# ADC.net
KiCad netlist of a schematic drawn in Altium Designer
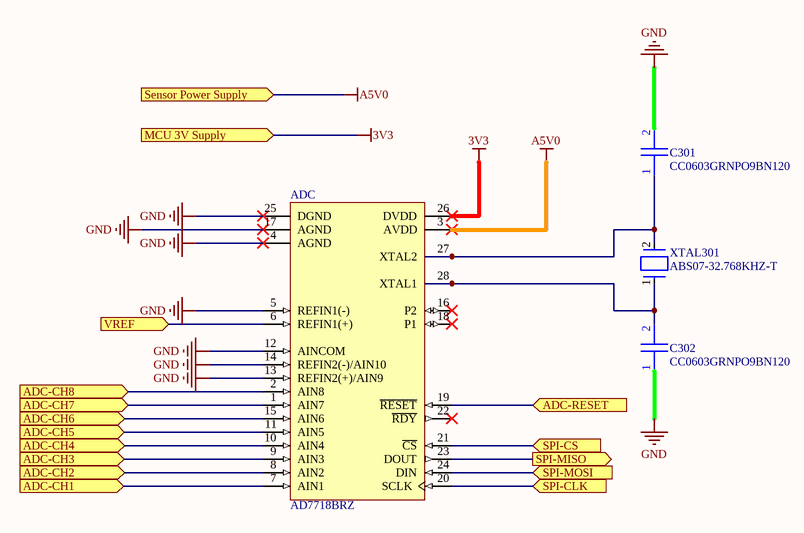
[diagram p0: ADC.SchDoc]

(export (version "E")
  (design (tool "Eeschema 10.0.6"))
  (components
    (comp (ref "ADC")
      (value "AD7718BRZ")
      (footprint "RW-28_L")
      (fields (field (name "GENERIC PART NUMBER") "AD7718") (field (name "MANUFACTURER") "Analog Devices"))
      (libsource (lib "Altium Content Vault") (part "ADI-AD7718-RW-28"))
    )
    (comp (ref "C301")
      (value "CC0603GRNPO9BN120")
      (footprint "CC0603GRNPO9BN120")
      (description "12pF 50V")
      (libsource (lib "ECEN403Sensors") (part "CC0603GRNPO9BN120"))
    )
    (comp (ref "C302")
      (value "CC0603GRNPO9BN120")
      (footprint "CC0603GRNPO9BN120")
      (description "12pF 50V")
      (libsource (lib "ECEN403Sensors") (part "CC0603GRNPO9BN120"))
    )
    (comp (ref "XTAL301")
      (value "ABS07-32.768KHZ-T")
      (footprint "FP-ABS07-MFG")
      (description "Crystal 32.768kHz ±20ppm (Tol) 12.5pF FUND 70kΩ 2-Pin CSMD T/R")
      (fields (field (name "TOLERANCE") "20ppm"))
      (libsource (lib "Altium Content Vault") (part "c23a69dc6c9e2f18f2079038eb95dd1"))
    )
  )
  (nets
    (net (code "1") (name "/ADC-CH1") (class "Default")
      (node (ref "ADC") (pin "7") (pinfunction "AIN1_7") (pintype "input"))
    )
    (net (code "2") (name "/ADC-CH2") (class "Default")
      (node (ref "ADC") (pin "8") (pinfunction "AIN2_8") (pintype "input"))
    )
    (net (code "3") (name "/ADC-CH3") (class "Default")
      (node (ref "ADC") (pin "9") (pinfunction "AIN3_9") (pintype "input"))
    )
    (net (code "4") (name "/ADC-CH4") (class "Default")
      (node (ref "ADC") (pin "10") (pinfunction "AIN4_10") (pintype "input"))
    )
    (net (code "5") (name "/ADC-CH5") (class "Default")
      (node (ref "ADC") (pin "11") (pinfunction "AIN5_11") (pintype "input"))
    )
    (net (code "6") (name "/ADC-CH6") (class "Default")
      (node (ref "ADC") (pin "15") (pinfunction "AIN6_15") (pintype "input"))
    )
    (net (code "7") (name "/ADC-CH7") (class "Default")
      (node (ref "ADC") (pin "1") (pinfunction "AIN7_1") (pintype "input"))
    )
    (net (code "8") (name "/ADC-CH8") (class "Default")
      (node (ref "ADC") (pin "2") (pinfunction "AIN8_2") (pintype "input"))
    )
    (net (code "9") (name "/ADC-RESET") (class "Default")
      (node (ref "ADC") (pin "19") (pinfunction "~{RESET}_19") (pintype "input"))
    )
    (net (code "10") (name "/SPI-CLK") (class "Default")
      (node (ref "ADC") (pin "20") (pinfunction "SCLK_20") (pintype "input"))
    )
    (net (code "11") (name "/SPI-CS") (class "Default")
      (node (ref "ADC") (pin "21") (pinfunction "~{CS}_21") (pintype "input"))
    )
    (net (code "12") (name "/SPI-MISO") (class "Default")
      (node (ref "ADC") (pin "23") (pinfunction "DOUT_23") (pintype "output"))
    )
    (net (code "13") (name "/SPI-MOSI") (class "Default")
      (node (ref "ADC") (pin "24") (pinfunction "DIN_24") (pintype "input"))
    )
    (net (code "14") (name "/VREF") (class "Default")
      (node (ref "ADC") (pin "6") (pinfunction "REFIN1(+)_6") (pintype "input"))
    )
    (net (code "15") (name "3V3") (class "Default")
      (node (ref "ADC") (pin "26") (pinfunction "DVDD_26") (pintype "power_in"))
    )
    (net (code "16") (name "A5V0") (class "Default")
      (node (ref "ADC") (pin "3") (pinfunction "AVDD_3") (pintype "power_in"))
    )
    (net (code "17") (name "GND") (class "Default")
      (node (ref "ADC") (pin "12") (pinfunction "AINCOM_12") (pintype "input"))
      (node (ref "ADC") (pin "13") (pinfunction "REFIN2(+)/AIN9_13") (pintype "input"))
      (node (ref "ADC") (pin "14") (pinfunction "REFIN2(-)/AIN10_14") (pintype "input"))
      (node (ref "ADC") (pin "17") (pinfunction "AGND_17") (pintype "power_in"))
      (node (ref "ADC") (pin "25") (pinfunction "DGND_25") (pintype "power_in"))
      (node (ref "ADC") (pin "4") (pinfunction "AGND_4") (pintype "power_in"))
      (node (ref "ADC") (pin "5") (pinfunction "REFIN1(-)_5") (pintype "input"))
      (node (ref "C301") (pin "2") (pinfunction "2_2") (pintype "passive"))
      (node (ref "C302") (pin "1") (pinfunction "1_1") (pintype "passive"))
    )
    (net (code "18") (name "Net-(ADC-XTAL1)") (class "Default")
      (node (ref "ADC") (pin "28") (pinfunction "XTAL1_28") (pintype "passive"))
      (node (ref "C302") (pin "2") (pinfunction "2_2") (pintype "passive"))
      (node (ref "XTAL301") (pin "1") (pinfunction "1_1") (pintype "passive"))
    )
    (net (code "19") (name "Net-(ADC-XTAL2)") (class "Default")
      (node (ref "ADC") (pin "27") (pinfunction "XTAL2_27") (pintype "passive"))
      (node (ref "C301") (pin "1") (pinfunction "1_1") (pintype "passive"))
      (node (ref "XTAL301") (pin "2") (pinfunction "2_2") (pintype "passive"))
    )
    (net (code "20") (name "unconnected-(ADC-P1-Pad18)") (class "Default")
      (node (ref "ADC") (pin "18") (pinfunction "P1_18") (pintype "bidirectional+no_connect"))
    )
    (net (code "21") (name "unconnected-(ADC-P2-Pad16)") (class "Default")
      (node (ref "ADC") (pin "16") (pinfunction "P2_16") (pintype "bidirectional+no_connect"))
    )
    (net (code "22") (name "unconnected-(ADC-~{RDY}-Pad22)") (class "Default")
      (node (ref "ADC") (pin "22") (pinfunction "~{RDY}_22") (pintype "output+no_connect"))
    )
  )
)
